# POF.net
KiCad netlist of a schematic drawn in Altium Designer
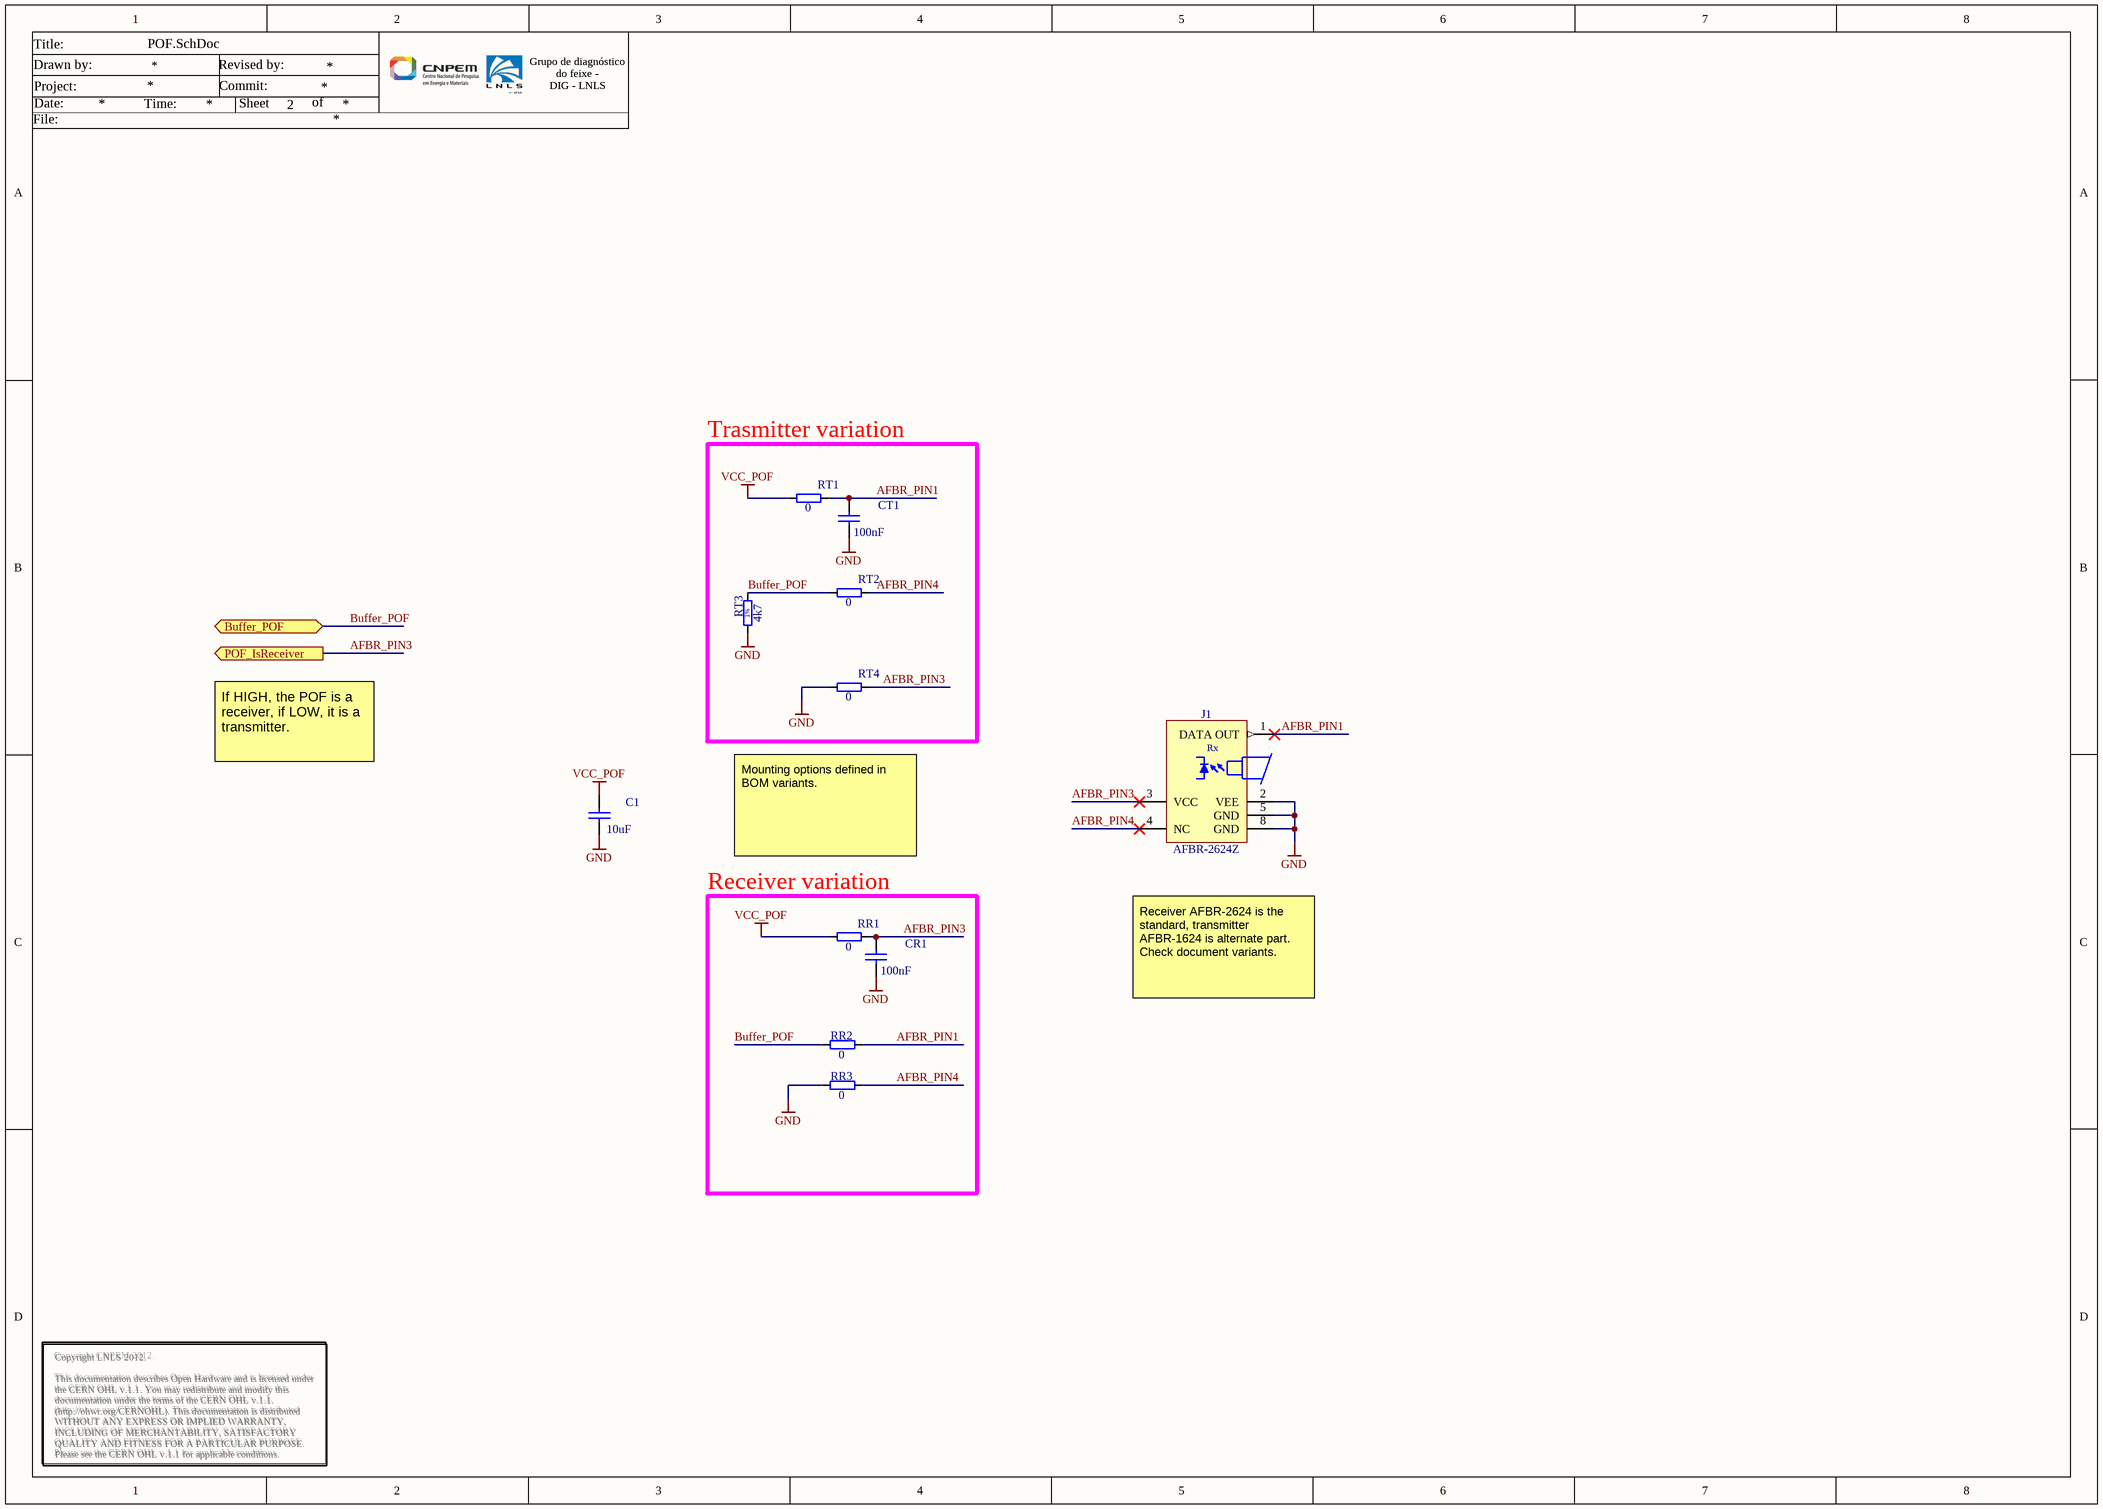
[diagram p0: POF.SchDoc]

(export (version "E")
  (design (tool "Eeschema 10.0.6"))
  (components
    (comp (ref "C1")
      (value "10uF")
      (footprint "CAPC2012X135N")
      (description "Non-polarised capacitor")
      (fields
        (field (name "PART NUMBER") "CC0805_10UF_10V_10%_X7R")
        (field (name "VOLTAGE") "10V")
        (field (name "AUTHOR") "CERN DEM JLC")
      )
      (libsource (lib "Capacitors") (part "Capacitor - non polarized"))
    )
    (comp (ref "CR1")
      (value "100nF")
      (footprint "CAPC1005X55N")
      (description "Non-polarised capacitor")
      (fields
        (field (name "PART NUMBER") "CC0402_100NF_16V_10%_X5R")
        (field (name "VOLTAGE") "16V")
        (field (name "AUTHOR") "CERN DEM JLC")
      )
      (libsource (lib "Capacitors") (part "Capacitor - non polarized"))
    )
    (comp (ref "CT1")
      (value "100nF")
      (footprint "CAPC1005X55N")
      (description "Non-polarised capacitor")
      (fields
        (field (name "PART NUMBER") "CC0402_100NF_16V_10%_X5R")
        (field (name "VOLTAGE") "16V")
        (field (name "AUTHOR") "CERN DEM JLC")
      )
      (libsource (lib "Capacitors") (part "Capacitor - non polarized"))
    )
    (comp (ref "J1")
      (value "AFBR-2624Z")
      (footprint "AFBR-x624Z")
      (description "DC-50MBd Versatile Link Fiber Optic Receiver for 1 mm POF and 200 µm PCS")
      (fields (field (name "MANUFACTURER") "AVAGO TECHNOLOGIES") (field (name "AUTHOR") "CERN DEM MR"))
      (libsource (lib "Connectors") (part "AFBR-26x4Z"))
    )
    (comp (ref "RR1")
      (value "0")
      (footprint "RESC1005X40N")
      (description "Resistor")
      (fields
        (field (name "PART NUMBER") "R0402_0R_JUMPER")
        (field (name "MANUFACTURER") "GENERIC")
        (field (name "AUTHOR") "CERN DEM JLC")
      )
      (libsource (lib "Resistors") (part "Resistor"))
    )
    (comp (ref "RR2")
      (value "0")
      (footprint "RESC1005X40N")
      (description "Resistor")
      (fields
        (field (name "PART NUMBER") "R0402_0R_JUMPER")
        (field (name "MANUFACTURER") "GENERIC")
        (field (name "AUTHOR") "CERN DEM JLC")
      )
      (libsource (lib "Resistors") (part "Resistor"))
    )
    (comp (ref "RR3")
      (value "0")
      (footprint "RESC1005X40N")
      (description "Resistor")
      (fields
        (field (name "PART NUMBER") "R0402_0R_JUMPER")
        (field (name "MANUFACTURER") "GENERIC")
        (field (name "AUTHOR") "CERN DEM JLC")
      )
      (libsource (lib "Resistors") (part "Resistor"))
    )
    (comp (ref "RT1")
      (value "0")
      (footprint "RESC1005X40N")
      (description "Resistor")
      (fields
        (field (name "PART NUMBER") "R0402_0R_JUMPER")
        (field (name "MANUFACTURER") "GENERIC")
        (field (name "AUTHOR") "CERN DEM JLC")
      )
      (libsource (lib "Resistors") (part "Resistor"))
    )
    (comp (ref "RT2")
      (value "0")
      (footprint "RESC1005X40N")
      (description "Resistor")
      (fields
        (field (name "PART NUMBER") "R0402_0R_JUMPER")
        (field (name "MANUFACTURER") "GENERIC")
        (field (name "AUTHOR") "CERN DEM JLC")
      )
      (libsource (lib "Resistors") (part "Resistor"))
    )
    (comp (ref "RT3")
      (value "4k7")
      (footprint "RESC1005X40N")
      (description "Resistor - 1%")
      (fields
        (field (name "PART NUMBER") "R0402_4K7_1%_0.0625W_100PPM")
        (field (name "POWER") "0.0625W")
        (field (name "AUTHOR") "CERN DEM JLC")
      )
      (libsource (lib "Resistors") (part "Resistor - 1%"))
    )
    (comp (ref "RT4")
      (value "0")
      (footprint "RESC1005X40N")
      (description "Resistor")
      (fields
        (field (name "PART NUMBER") "R0402_0R_JUMPER")
        (field (name "MANUFACTURER") "GENERIC")
        (field (name "AUTHOR") "CERN DEM JLC")
      )
      (libsource (lib "Resistors") (part "Resistor"))
    )
  )
  (nets
    (net (code "1") (name "/AFBR_PIN1") (class "Default")
      (node (ref "CT1") (pin "2") (pinfunction "2_2") (pintype "passive"))
      (node (ref "J1") (pin "1") (pinfunction "DATA_OUT_1") (pintype "output"))
      (node (ref "RR2") (pin "2") (pinfunction "2_2") (pintype "passive"))
      (node (ref "RT1") (pin "2") (pinfunction "2_2") (pintype "passive"))
    )
    (net (code "2") (name "/AFBR_PIN3") (class "Default")
      (node (ref "CR1") (pin "2") (pinfunction "2_2") (pintype "passive"))
      (node (ref "J1") (pin "3") (pinfunction "VCC_3") (pintype "power_in"))
      (node (ref "RR1") (pin "2") (pinfunction "2_2") (pintype "passive"))
      (node (ref "RT4") (pin "2") (pinfunction "2_2") (pintype "passive"))
    )
    (net (code "3") (name "/AFBR_PIN4") (class "Default")
      (node (ref "J1") (pin "4") (pinfunction "NC_4") (pintype "passive"))
      (node (ref "RR3") (pin "2") (pinfunction "2_2") (pintype "passive"))
      (node (ref "RT2") (pin "2") (pinfunction "2_2") (pintype "passive"))
    )
    (net (code "4") (name "/Buffer_POF") (class "Default")
      (node (ref "RR2") (pin "1") (pinfunction "1_1") (pintype "passive"))
      (node (ref "RT2") (pin "1") (pinfunction "1_1") (pintype "passive"))
      (node (ref "RT3") (pin "2") (pinfunction "2_2") (pintype "passive"))
    )
    (net (code "5") (name "GND") (class "Default")
      (node (ref "C1") (pin "1") (pinfunction "1_1") (pintype "passive"))
      (node (ref "CR1") (pin "1") (pinfunction "1_1") (pintype "passive"))
      (node (ref "CT1") (pin "1") (pinfunction "1_1") (pintype "passive"))
      (node (ref "J1") (pin "2") (pinfunction "VEE_2") (pintype "power_in"))
      (node (ref "J1") (pin "5") (pinfunction "GND_5") (pintype "power_in"))
      (node (ref "J1") (pin "8") (pinfunction "GND_8") (pintype "power_in"))
      (node (ref "RR3") (pin "1") (pinfunction "1_1") (pintype "passive"))
      (node (ref "RT3") (pin "1") (pinfunction "1_1") (pintype "passive"))
      (node (ref "RT4") (pin "1") (pinfunction "1_1") (pintype "passive"))
    )
    (net (code "6") (name "VCC_POF") (class "Default")
      (node (ref "C1") (pin "2") (pinfunction "2_2") (pintype "passive"))
      (node (ref "RR1") (pin "1") (pinfunction "1_1") (pintype "passive"))
      (node (ref "RT1") (pin "1") (pinfunction "1_1") (pintype "passive"))
    )
  )
)
